# Sound_Light_IC_evaluation_board.net
KiCad netlist of a schematic drawn in Altium Designer
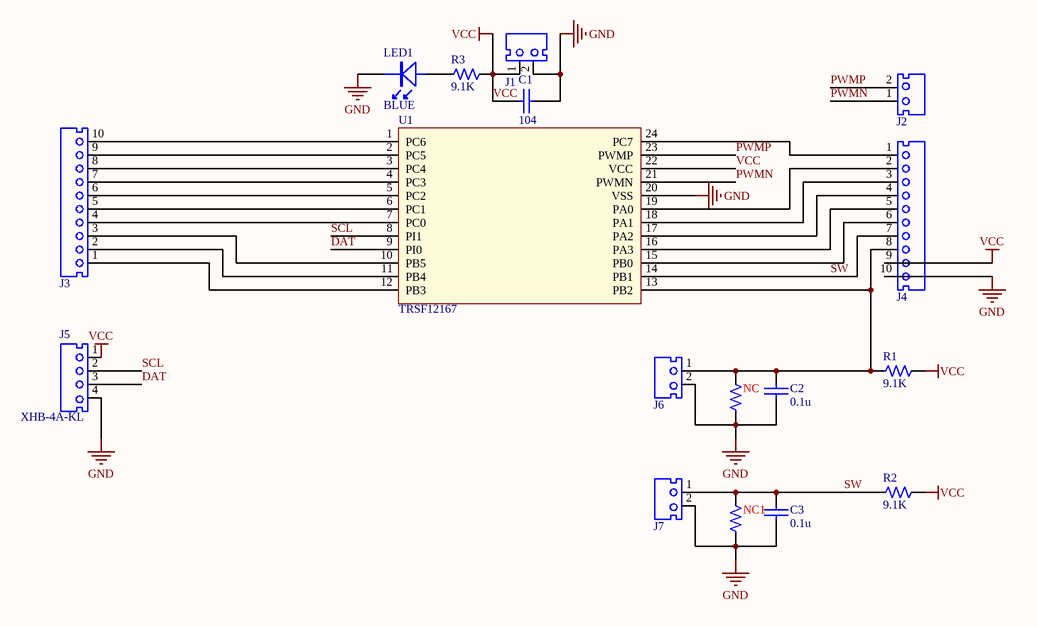
[diagram p0: Sound&Light IC evaluation board.SchDoc]

(export (version "E")
  (design (tool "Eeschema 10.0.6"))
  (components
    (comp (ref "C1")
      (value "104")
      (footprint "CAPC0603-RW")
      (description "CAP X7R .01UF 50V +-5% 0603 WALSIN L")
      (fields
        (field (name "MFG") "WALSIN")
        (field (name "TOLERANCE") "5%")
        (field (name "CREATE_NAME") "Nathan")
      )
      (libsource (lib "P-Capacitors") (part "CAP0603 0.01uF 50V 5%_X7R_WALSIN"))
    )
    (comp (ref "C2")
      (value "0.1u")
      (footprint "CAPC0603-RW")
      (description "CAP X7R .01UF 50V +-5% 0603 WALSIN L")
      (fields
        (field (name "MFG") "WALSIN")
        (field (name "TOLERANCE") "5%")
        (field (name "CREATE_NAME") "Nathan")
      )
      (libsource (lib "P-Capacitors") (part "CAP0603 0.01uF 50V 5%_X7R_WALSIN"))
    )
    (comp (ref "C3")
      (value "0.1u")
      (footprint "CAPC0603-RW")
      (description "CAP X7R .01UF 50V +-5% 0603 WALSIN L")
      (fields
        (field (name "MFG") "WALSIN")
        (field (name "TOLERANCE") "5%")
        (field (name "CREATE_NAME") "Nathan")
      )
      (libsource (lib "P-Capacitors") (part "CAP0603 0.01uF 50V 5%_X7R_WALSIN"))
    )
    (comp (ref "J1")
      (value "T690300125300")
      (footprint "CONN 2P PH=2.5mm HAA250A-2 WHITE")
      (description "CONNECTOR HA2.5 2PIN BLACK K")
      (fields
        (field (name "MFG") "金瑞康")
        (field (name "MFG PART") "HAA250A-2 BLACK")
        (field (name "CREATE_NAME") "Nathan")
      )
      (libsource (lib "C-Connector") (part "CONN 2P PH=2.5mm HAA250A-2 BLACK"))
    )
    (comp (ref "J2")
      (value "T690300125300")
      (footprint "CONN 2P PH=2.5mm HAA250A-2 WHITE")
      (description "CONNECTOR HA2.5 2PIN BLACK K")
      (fields
        (field (name "MFG") "金瑞康")
        (field (name "MFG PART") "HAA250A-2 BLACK")
        (field (name "CREATE_NAME") "Nathan")
      )
      (libsource (lib "C-Connector") (part "CONN 2P PH=2.5mm HAA250A-2 BLACK"))
    )
    (comp (ref "J3")
      (value "T690300105400")
      (footprint "CONN 10P PH=2.5mm ST CI2210P1VK0-NH")
      (description "WTB CONN. 2.5MM 10PIN CI2210P1VK0-NH CV G")
      (fields
        (field (name "MFG") "CVILUX")
        (field (name "MFG PART") "CI2210P1VK0-NH")
        (field (name "CREATE_NAME") "Nathan")
      )
      (libsource (lib "C-Connector") (part "CONN 10P PH=2.5mm ST CI2210P1VK0-NH"))
    )
    (comp (ref "J4")
      (value "T690300105400")
      (footprint "CONN 10P PH=2.5mm ST CI2210P1VK0-NH")
      (description "WTB CONN. 2.5MM 10PIN CI2210P1VK0-NH CV G")
      (fields
        (field (name "MFG") "CVILUX")
        (field (name "MFG PART") "CI2210P1VK0-NH")
        (field (name "CREATE_NAME") "Nathan")
      )
      (libsource (lib "C-Connector") (part "CONN 10P PH=2.5mm ST CI2210P1VK0-NH"))
    )
    (comp (ref "J5")
      (value "T690300127400")
      (footprint "CONN 4P PH=2.5mm XHB-4A-KL")
      (description "CONNECTOR 4PIN P 2.54MM 180° K")
      (fields
        (field (name "MFG") "金佳")
        (field (name "MFG PART") "XHB-4A-KL")
        (field (name "CREATE_NAME") "Nathan")
      )
      (libsource (lib "C-Connector") (part "CONN 4P PH=2.5mm XHB-4A-KL"))
    )
    (comp (ref "J6")
      (value "T690300125300")
      (footprint "CONN 2P PH=2.5mm HAA250A-2 WHITE")
      (description "CONNECTOR HA2.5 2PIN BLACK K")
      (fields
        (field (name "MFG") "金瑞康")
        (field (name "MFG PART") "HAA250A-2 BLACK")
        (field (name "CREATE_NAME") "Nathan")
      )
      (libsource (lib "C-Connector") (part "CONN 2P PH=2.5mm HAA250A-2 BLACK"))
    )
    (comp (ref "J7")
      (value "T690300125300")
      (footprint "CONN 2P PH=2.5mm HAA250A-2 WHITE")
      (description "CONNECTOR HA2.5 2PIN BLACK K")
      (fields
        (field (name "MFG") "金瑞康")
        (field (name "MFG PART") "HAA250A-2 BLACK")
        (field (name "CREATE_NAME") "Nathan")
      )
      (libsource (lib "C-Connector") (part "CONN 2P PH=2.5mm HAA250A-2 BLACK"))
    )
    (comp (ref "LED1")
      (value "T575011480204")
      (footprint "LED0603_BLUE")
      (description "LED 465 0603 LTST-C193TBK LITEON ( L")
      (fields
        (field (name "MFG PART") "LTST-C193TBKT-5A")
        (field (name "MFG") "LITEON (光寶)")
        (field (name "COLOR") "BLUE")
        (field (name "CREATE_NAME") "Nathan")
      )
      (libsource (lib "K-LED-FUSE") (part "LED0603B_LTST-C193TBKT-5A"))
    )
    (comp (ref "NC")
      (value "T502294202399")
      (footprint "0603-RW")
      (description "CHIP 29.4K OHM 100PPM +-1% 0603 WALS L")
      (fields (field (name "POWER") "1/10W") (field (name "MFG") "WALSIN") (field (name "CREATE_NAME") "Tom"))
      (libsource (lib "Q-Resistors") (part "RES0603 1/10W +-0.1% 29.4K OHM 100PPM"))
    )
    (comp (ref "NC1")
      (value "T502294202399")
      (footprint "0603-RW")
      (description "CHIP 29.4K OHM 100PPM +-1% 0603 WALS L")
      (fields (field (name "POWER") "1/10W") (field (name "MFG") "WALSIN") (field (name "CREATE_NAME") "Tom"))
      (libsource (lib "Q-Resistors") (part "RES0603 1/10W +-0.1% 29.4K OHM 100PPM"))
    )
    (comp (ref "R1")
      (value "9.1K")
      (footprint "0603-RW")
      (description "CHIP 29.4K OHM 100PPM +-1% 0603 WALS L")
      (fields (field (name "POWER") "1/10W") (field (name "MFG") "WALSIN") (field (name "CREATE_NAME") "Tom"))
      (libsource (lib "Q-Resistors") (part "RES0603 1/10W +-0.1% 29.4K OHM 100PPM"))
    )
    (comp (ref "R2")
      (value "9.1K")
      (footprint "0603-RW")
      (description "CHIP 29.4K OHM 100PPM +-1% 0603 WALS L")
      (fields (field (name "POWER") "1/10W") (field (name "MFG") "WALSIN") (field (name "CREATE_NAME") "Tom"))
      (libsource (lib "Q-Resistors") (part "RES0603 1/10W +-0.1% 29.4K OHM 100PPM"))
    )
    (comp (ref "R3")
      (value "9.1K")
      (footprint "0603-RW")
      (description "CHIP 29.4K OHM 100PPM +-1% 0603 WALS L")
      (fields (field (name "POWER") "1/10W") (field (name "MFG") "WALSIN") (field (name "CREATE_NAME") "Tom"))
      (libsource (lib "Q-Resistors") (part "RES0603 1/10W +-0.1% 29.4K OHM 100PPM"))
    )
    (comp (ref "U1")
      (value "BS86C08C 24SSOP")
      (footprint "SSOP24(150mil)")
      (description "BS86C08C_24SSOP")
      (fields
        (field (name "MFG") "HOLTEK")
        (field (name "MFG PART") "TRSF12167")
        (field (name "CREATE_NAME") "Nathan")
      )
      (libsource (lib "R-Semiconductors") (part "BS86C08C 24SSOP"))
    )
  )
  (nets
    (net (code "1") (name "/DAT") (class "Default")
      (node (ref "J5") (pin "3") (pinfunction "3_3") (pintype "passive"))
      (node (ref "U1") (pin "9") (pinfunction "PI0_9") (pintype "passive"))
    )
    (net (code "2") (name "/PWMN") (class "Default")
      (node (ref "J2") (pin "1") (pinfunction "1_1") (pintype "passive"))
      (node (ref "U1") (pin "21") (pinfunction "PWMN_21") (pintype "passive"))
    )
    (net (code "3") (name "/PWMP") (class "Default")
      (node (ref "J2") (pin "2") (pinfunction "2_2") (pintype "passive"))
      (node (ref "U1") (pin "23") (pinfunction "PWMP_23") (pintype "passive"))
    )
    (net (code "4") (name "/SCL") (class "Default")
      (node (ref "J5") (pin "2") (pinfunction "2_2") (pintype "passive"))
      (node (ref "U1") (pin "8") (pinfunction "PI1_8") (pintype "passive"))
    )
    (net (code "5") (name "/SW") (class "Default")
      (node (ref "C3") (pin "2") (pinfunction "2_2") (pintype "passive"))
      (node (ref "J4") (pin "7") (pinfunction "7_7") (pintype "passive"))
      (node (ref "J7") (pin "1") (pinfunction "1_1") (pintype "passive"))
      (node (ref "NC1") (pin "2") (pinfunction "2_2") (pintype "passive"))
      (node (ref "R2") (pin "1") (pinfunction "1_1") (pintype "passive"))
      (node (ref "U1") (pin "14") (pinfunction "PB1_14") (pintype "passive"))
    )
    (net (code "6") (name "GND") (class "Default")
      (node (ref "C1") (pin "1") (pinfunction "1_1") (pintype "passive"))
      (node (ref "C2") (pin "1") (pinfunction "1_1") (pintype "passive"))
      (node (ref "C3") (pin "1") (pinfunction "1_1") (pintype "passive"))
      (node (ref "J1") (pin "2") (pinfunction "2_2") (pintype "passive"))
      (node (ref "J4") (pin "10") (pinfunction "10_10") (pintype "passive"))
      (node (ref "J5") (pin "4") (pinfunction "4_4") (pintype "passive"))
      (node (ref "J6") (pin "2") (pinfunction "2_2") (pintype "passive"))
      (node (ref "J7") (pin "2") (pinfunction "2_2") (pintype "passive"))
      (node (ref "LED1") (pin "2") (pinfunction "K_2") (pintype "passive"))
      (node (ref "NC") (pin "1") (pinfunction "1_1") (pintype "passive"))
      (node (ref "NC1") (pin "1") (pinfunction "1_1") (pintype "passive"))
      (node (ref "U1") (pin "20") (pinfunction "VSS_20") (pintype "passive"))
    )
    (net (code "7") (name "Net-(LED1-A)") (class "Default")
      (node (ref "LED1") (pin "1") (pinfunction "A_1") (pintype "passive"))
      (node (ref "R3") (pin "1") (pinfunction "1_1") (pintype "passive"))
    )
    (net (code "8") (name "Net-(U1-PA0)") (class "Default")
      (node (ref "J4") (pin "2") (pinfunction "2_2") (pintype "passive"))
      (node (ref "U1") (pin "19") (pinfunction "PA0_19") (pintype "passive"))
    )
    (net (code "9") (name "Net-(U1-PA1)") (class "Default")
      (node (ref "J4") (pin "3") (pinfunction "3_3") (pintype "passive"))
      (node (ref "U1") (pin "18") (pinfunction "PA1_18") (pintype "passive"))
    )
    (net (code "10") (name "Net-(U1-PA2)") (class "Default")
      (node (ref "J4") (pin "4") (pinfunction "4_4") (pintype "passive"))
      (node (ref "U1") (pin "17") (pinfunction "PA2_17") (pintype "passive"))
    )
    (net (code "11") (name "Net-(U1-PA3)") (class "Default")
      (node (ref "J4") (pin "5") (pinfunction "5_5") (pintype "passive"))
      (node (ref "U1") (pin "16") (pinfunction "PA3_16") (pintype "passive"))
    )
    (net (code "12") (name "Net-(U1-PB0)") (class "Default")
      (node (ref "J4") (pin "6") (pinfunction "6_6") (pintype "passive"))
      (node (ref "U1") (pin "15") (pinfunction "PB0_15") (pintype "passive"))
    )
    (net (code "13") (name "Net-(U1-PB2)") (class "Default")
      (node (ref "C2") (pin "2") (pinfunction "2_2") (pintype "passive"))
      (node (ref "J4") (pin "8") (pinfunction "8_8") (pintype "passive"))
      (node (ref "J6") (pin "1") (pinfunction "1_1") (pintype "passive"))
      (node (ref "NC") (pin "2") (pinfunction "2_2") (pintype "passive"))
      (node (ref "R1") (pin "1") (pinfunction "1_1") (pintype "passive"))
      (node (ref "U1") (pin "13") (pinfunction "PB2_13") (pintype "passive"))
    )
    (net (code "14") (name "Net-(U1-PB3)") (class "Default")
      (node (ref "J3") (pin "1") (pinfunction "1_1") (pintype "passive"))
      (node (ref "U1") (pin "12") (pinfunction "PB3_12") (pintype "passive"))
    )
    (net (code "15") (name "Net-(U1-PB4)") (class "Default")
      (node (ref "J3") (pin "2") (pinfunction "2_2") (pintype "passive"))
      (node (ref "U1") (pin "11") (pinfunction "PB4_11") (pintype "passive"))
    )
    (net (code "16") (name "Net-(U1-PB5)") (class "Default")
      (node (ref "J3") (pin "3") (pinfunction "3_3") (pintype "passive"))
      (node (ref "U1") (pin "10") (pinfunction "PB5_10") (pintype "passive"))
    )
    (net (code "17") (name "Net-(U1-PC0)") (class "Default")
      (node (ref "J3") (pin "4") (pinfunction "4_4") (pintype "passive"))
      (node (ref "U1") (pin "7") (pinfunction "PC0_7") (pintype "passive"))
    )
    (net (code "18") (name "Net-(U1-PC1)") (class "Default")
      (node (ref "J3") (pin "5") (pinfunction "5_5") (pintype "passive"))
      (node (ref "U1") (pin "6") (pinfunction "PC1_6") (pintype "passive"))
    )
    (net (code "19") (name "Net-(U1-PC2)") (class "Default")
      (node (ref "J3") (pin "6") (pinfunction "6_6") (pintype "passive"))
      (node (ref "U1") (pin "5") (pinfunction "PC2_5") (pintype "passive"))
    )
    (net (code "20") (name "Net-(U1-PC3)") (class "Default")
      (node (ref "J3") (pin "7") (pinfunction "7_7") (pintype "passive"))
      (node (ref "U1") (pin "4") (pinfunction "PC3_4") (pintype "passive"))
    )
    (net (code "21") (name "Net-(U1-PC4)") (class "Default")
      (node (ref "J3") (pin "8") (pinfunction "8_8") (pintype "passive"))
      (node (ref "U1") (pin "3") (pinfunction "PC4_3") (pintype "passive"))
    )
    (net (code "22") (name "Net-(U1-PC5)") (class "Default")
      (node (ref "J3") (pin "9") (pinfunction "9_9") (pintype "passive"))
      (node (ref "U1") (pin "2") (pinfunction "PC5_2") (pintype "passive"))
    )
    (net (code "23") (name "Net-(U1-PC6)") (class "Default")
      (node (ref "J3") (pin "10") (pinfunction "10_10") (pintype "passive"))
      (node (ref "U1") (pin "1") (pinfunction "PC6_1") (pintype "passive"))
    )
    (net (code "24") (name "Net-(U1-PC7)") (class "Default")
      (node (ref "J4") (pin "1") (pinfunction "1_1") (pintype "passive"))
      (node (ref "U1") (pin "24") (pinfunction "PC7_24") (pintype "passive"))
    )
    (net (code "25") (name "VCC") (class "Default")
      (node (ref "C1") (pin "2") (pinfunction "2_2") (pintype "passive"))
      (node (ref "J1") (pin "1") (pinfunction "1_1") (pintype "passive"))
      (node (ref "J4") (pin "9") (pinfunction "9_9") (pintype "passive"))
      (node (ref "J5") (pin "1") (pinfunction "1_1") (pintype "passive"))
      (node (ref "R1") (pin "2") (pinfunction "2_2") (pintype "passive"))
      (node (ref "R2") (pin "2") (pinfunction "2_2") (pintype "passive"))
      (node (ref "R3") (pin "2") (pinfunction "2_2") (pintype "passive"))
      (node (ref "U1") (pin "22") (pinfunction "VCC_22") (pintype "passive"))
    )
  )
)
